# connectorOut.net
KiCad netlist of a schematic drawn in Altium Designer
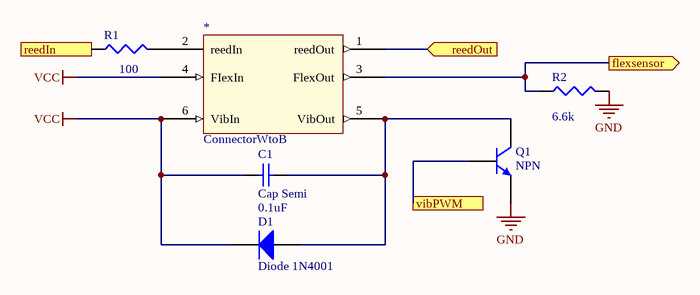
[diagram p0: connectorOut.SchDoc]

(export (version "E")
  (design (tool "Eeschema 10.0.6"))
  (components
    (comp (ref "*")
      (value "ConnectorWtoB")
      (footprint "Connector_wire_to_PCB")
      (libsource (lib "HGCDLibrary") (part "ConnectorWtoB"))
    )
    (comp (ref "C1")
      (value "Cap Semi")
      (footprint "C1206")
      (description "Capacitor (Semiconductor SIM Model)")
      (fields (field (name "ALTIUM_VALUE") "0.1uF") (field (name "PUBLISHER") "Altium Limited"))
      (libsource (lib "Miscellaneous Devices") (part "Cap Semi"))
    )
    (comp (ref "D1")
      (value "Diode 1N4001")
      (footprint "DO-41")
      (description "1 Amp General Purpose Rectifier")
      (fields (field (name "PUBLISHER") "Altium Limited"))
      (libsource (lib "Miscellaneous Devices") (part "Diode 1N4001"))
    )
    (comp (ref "Q1")
      (value "NPN")
      (footprint "TO-226-AA")
      (description "NPN Bipolar Transistor")
      (fields (field (name "PUBLISHER") "Altium Limited"))
      (libsource (lib "Miscellaneous Devices") (part "NPN"))
    )
    (comp (ref "R1")
      (value "100")
      (footprint "J1-0603")
      (description "Resistor")
      (fields (field (name "PUBLISHER") "Altium Limited"))
      (libsource (lib "Miscellaneous Devices") (part "Res3"))
    )
    (comp (ref "R2")
      (value "6.6k")
      (footprint "J1-0603")
      (description "Resistor")
      (fields (field (name "Comment") "Res3") (field (name "PUBLISHER") "Altium Limited"))
      (libsource (lib "Miscellaneous Devices") (part "Res3"))
    )
  )
  (nets
    (net (code "1") (name "/flexsensor") (class "Default")
      (node (ref "*") (pin "3") (pinfunction "FlexOut_3") (pintype "output"))
      (node (ref "R2") (pin "1") (pinfunction "1_1") (pintype "passive"))
    )
    (net (code "2") (name "/reedIn") (class "Default")
      (node (ref "R1") (pin "1") (pinfunction "1_1") (pintype "passive"))
    )
    (net (code "3") (name "/reedOut") (class "Default")
      (node (ref "*") (pin "1") (pinfunction "reedOut_1") (pintype "output"))
    )
    (net (code "4") (name "/vibPWM") (class "Default")
      (node (ref "Q1") (pin "2") (pinfunction "B_2") (pintype "passive"))
    )
    (net (code "5") (name "GND") (class "Default")
      (node (ref "Q1") (pin "3") (pinfunction "E_3") (pintype "passive"))
      (node (ref "R2") (pin "2") (pinfunction "2_2") (pintype "passive"))
    )
    (net (code "6") (name "Net-(*-VibOut)") (class "Default")
      (node (ref "*") (pin "5") (pinfunction "VibOut_5") (pintype "output"))
      (node (ref "C1") (pin "2") (pinfunction "2_2") (pintype "passive"))
      (node (ref "D1") (pin "1") (pinfunction "A_1") (pintype "passive"))
      (node (ref "Q1") (pin "1") (pinfunction "C_1") (pintype "passive"))
    )
    (net (code "7") (name "Net-(*-reedIn)") (class "Default")
      (node (ref "*") (pin "2") (pinfunction "reedIn_2") (pintype "open_collector"))
      (node (ref "R1") (pin "2") (pinfunction "2_2") (pintype "passive"))
    )
    (net (code "8") (name "VCC") (class "Default")
      (node (ref "*") (pin "4") (pinfunction "FIexIn_4") (pintype "input"))
      (node (ref "*") (pin "6") (pinfunction "VibIn_6") (pintype "input"))
      (node (ref "C1") (pin "1") (pinfunction "1_1") (pintype "passive"))
      (node (ref "D1") (pin "2") (pinfunction "K_2") (pintype "passive"))
    )
  )
)
